# DIN4-break.net
KiCad netlist of a schematic drawn in EAGLE
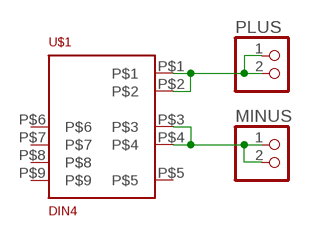
[diagram p0: schematic, sheet 1]

(export (version "E")
  (design (tool "Eeschema 10.0.6"))
  (components
    (comp (ref "MINUS")
      (value "PINHD-1X2")
      (footprint "eagle-import:1X02")
      (libsource (lib "eagle-import") (part "PINHD-1X2"))
    )
    (comp (ref "PLUS")
      (value "PINHD-1X2")
      (footprint "eagle-import:1X02")
      (libsource (lib "eagle-import") (part "PINHD-1X2"))
    )
    (comp (ref "U$1")
      (value "DIN4")
      (footprint "eagle-import:DIN4")
      (libsource (lib "eagle-import") (part "DIN4"))
    )
  )
  (nets
    (net (code "1") (name "Net-(MINUS-Pad1)") (class "Default")
      (node (ref "MINUS") (pin "1") (pinfunction "1_1") (pintype "passive"))
      (node (ref "MINUS") (pin "2") (pinfunction "2_2") (pintype "passive"))
      (node (ref "U$1") (pin "P$3") (pinfunction "P$3_P$3") (pintype "bidirectional"))
      (node (ref "U$1") (pin "P$4") (pinfunction "P$4_P$4") (pintype "bidirectional"))
    )
    (net (code "2") (name "Net-(PLUS-Pad1)") (class "Default")
      (node (ref "PLUS") (pin "1") (pinfunction "1_1") (pintype "passive"))
      (node (ref "PLUS") (pin "2") (pinfunction "2_2") (pintype "passive"))
      (node (ref "U$1") (pin "P$1") (pinfunction "P$1_P$1") (pintype "bidirectional"))
      (node (ref "U$1") (pin "P$2") (pinfunction "P$2_P$2") (pintype "bidirectional"))
    )
    (net (code "3") (name "unconnected-(U$1-PadP$5)") (class "Default")
      (node (ref "U$1") (pin "P$5") (pinfunction "P$5_P$5") (pintype "bidirectional"))
    )
    (net (code "4") (name "unconnected-(U$1-PadP$6)") (class "Default")
      (node (ref "U$1") (pin "P$6") (pinfunction "P$6_P$6") (pintype "bidirectional"))
    )
    (net (code "5") (name "unconnected-(U$1-PadP$7)") (class "Default")
      (node (ref "U$1") (pin "P$7") (pinfunction "P$7_P$7") (pintype "bidirectional"))
    )
    (net (code "6") (name "unconnected-(U$1-PadP$8)") (class "Default")
      (node (ref "U$1") (pin "P$8") (pinfunction "P$8_P$8") (pintype "bidirectional"))
    )
    (net (code "7") (name "unconnected-(U$1-PadP$9)") (class "Default")
      (node (ref "U$1") (pin "P$9") (pinfunction "P$9_P$9") (pintype "bidirectional"))
    )
  )
)
